# CAN.net
KiCad netlist of a schematic drawn in Altium Designer
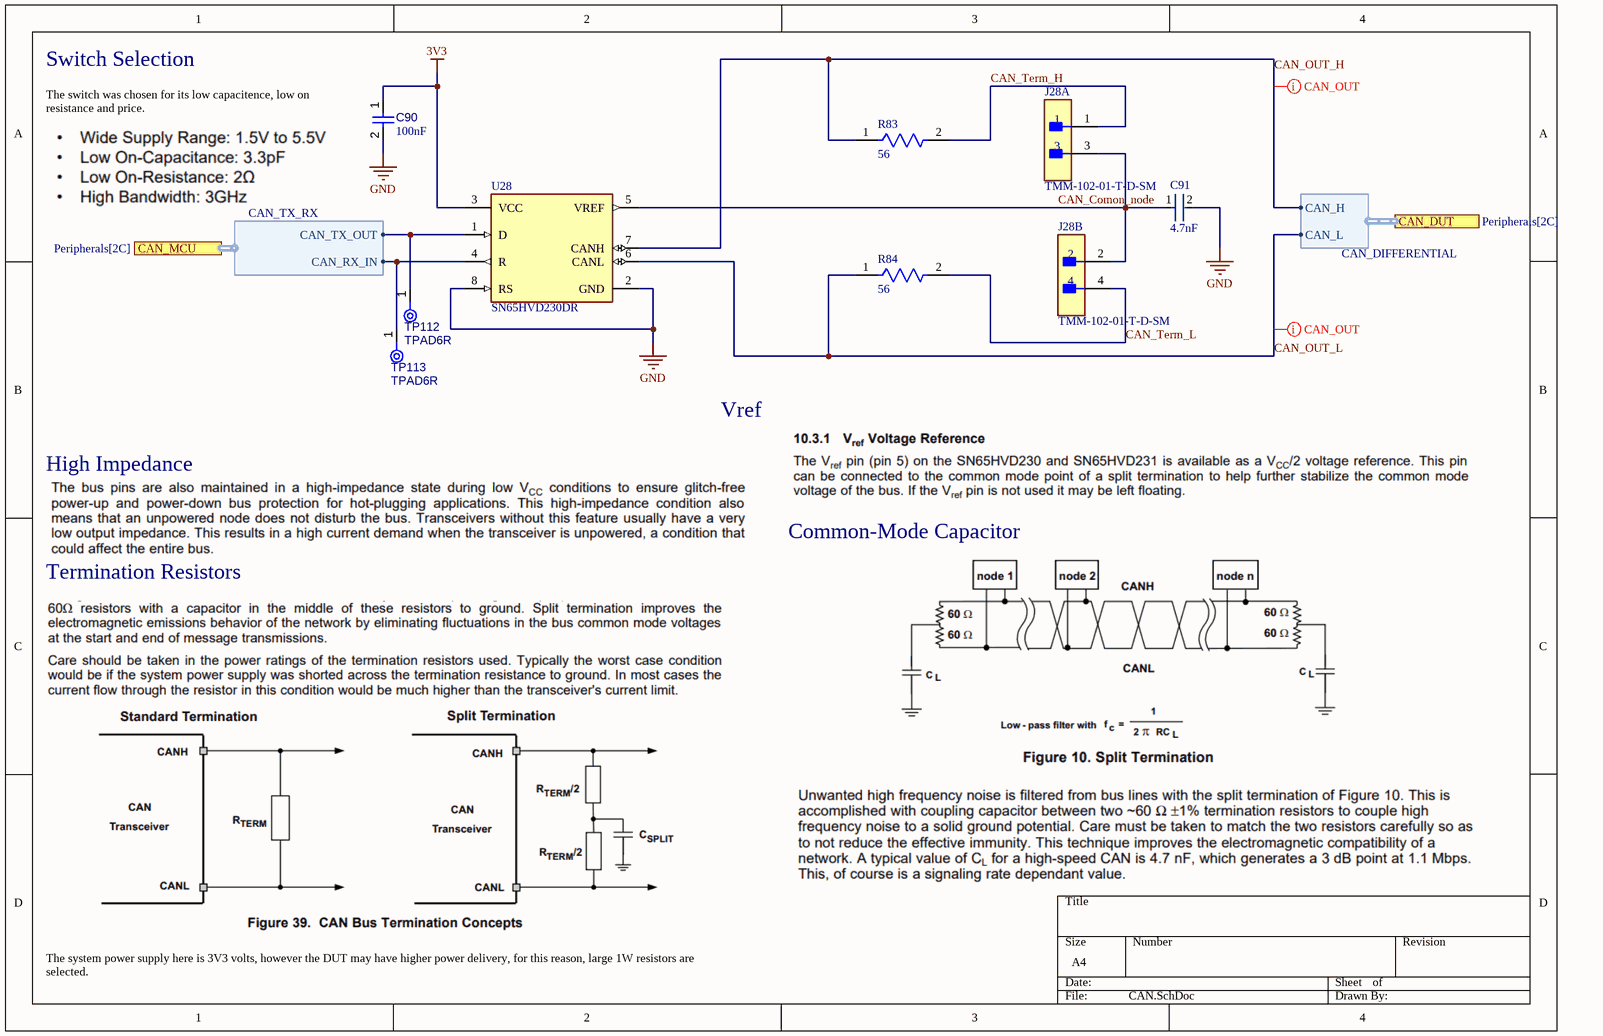
[diagram p0:  CAN.SchDoc]

(export (version "E")
  (design (tool "Eeschema 10.0.6"))
  (components
    (comp (ref "C90")
      (value "100nF")
      (footprint "CAPC1608X90X40NL10T20")
      (description "Chip Capacitor, 100 nF, +/- 10%, 50 V, 0603 (1608 Metric)")
      (fields (field (name "TOLERANCE") "10%") (field (name "Comment") "Capacitor 100 nF +/-10% 50 V 0603"))
      (libsource (lib "HIL RIG FYP") (part "CAP-NP-2"))
    )
    (comp (ref "C91")
      (value "4.7nF")
      (footprint "FP-C0603C-CF-MFG")
      (description "Ceramic Capacitor, Multilayer, Ceramic, 25V, 10% +Tol, 10% -Tol, C0G, 30Ppm/Cel Tc, 0.0047Uf,")
      (fields (field (name "TOLERANCE") "10%") (field (name "Comment") "C0603C472K3GACTU"))
      (libsource (lib "HIL RIG FYP") (part "b4654b650e69147ec39a6b967a45e02"))
    )
    (comp (ref "J28")
      (value "TMM-102-01-T-D-SM")
      (footprint "FP-TMM-102-01-T-D-SM-MFG")
      (description "CONN HEADER SMD 4POS 2MM")
      (libsource (lib "Altium Content Vault") (part "1621473add15499e993d6bbd36d0f06"))
    )
    (comp (ref "R83")
      (value "56")
      (footprint "FP-AC2512-IPC_C")
      (description "1W Thick Film Resistors 200V ±100ppm/℃ ±1% 56Ω 2512 Chip Resistor - Surface Mount ROHS")
      (fields (field (name "TOLERANCE") "1%") (field (name "Comment") "AC2512FK-0756RL"))
      (libsource (lib "HIL RIG FYP") (part "1029c3af85768c4190bb7ad29bc67b5"))
    )
    (comp (ref "R84")
      (value "56")
      (footprint "FP-AC2512-IPC_C")
      (description "1W Thick Film Resistors 200V ±100ppm/℃ ±1% 56Ω 2512 Chip Resistor - Surface Mount ROHS")
      (fields (field (name "TOLERANCE") "1%") (field (name "Comment") "AC2512FK-0756RL"))
      (libsource (lib "HIL RIG FYP") (part "1029c3af85768c4190bb7ad29bc67b5"))
    )
    (comp (ref "TP112")
      (value "TPAD6R")
      (footprint "TP06R")
      (description "0.6mm round")
      (libsource (lib "HIL RIG FYP") (part "CMP-001-0001-4"))
    )
    (comp (ref "TP113")
      (value "TPAD6R")
      (footprint "TP06R")
      (description "0.6mm round")
      (libsource (lib "HIL RIG FYP") (part "CMP-001-0001-4"))
    )
    (comp (ref "U28")
      (value "SN65HVD230DR")
      (footprint "FP-D0008A-IPC_A")
      (description "3.3 V CAN Transceiver with Standby Mode 8-SOIC -40 to 85")
      (libsource (lib "HIL RIG FYP") (part "43b56812b1adf0e60a7acfb7c27ab91"))
    )
  )
  (nets
    (net (code "3") (name "/CAN_Comon_node") (class "Default")
      (node (ref "C91") (pin "1") (pinfunction "1_1") (pintype "passive"))
      (node (ref "J28") (pin "2") (pinfunction "2_2") (pintype "passive"))
      (node (ref "J28") (pin "3") (pinfunction "3_3") (pintype "passive"))
      (node (ref "U28") (pin "5") (pinfunction "VREF_5") (pintype "output"))
    )
    (net (code "4") (name "/CAN_OUT_H") (class "Default")
      (node (ref "R83") (pin "1") (pinfunction "1_1") (pintype "passive"))
      (node (ref "U28") (pin "7") (pinfunction "CANH_7") (pintype "bidirectional"))
    )
    (net (code "5") (name "/CAN_OUT_L") (class "Default")
      (node (ref "R84") (pin "1") (pinfunction "1_1") (pintype "passive"))
      (node (ref "U28") (pin "6") (pinfunction "CANL_6") (pintype "bidirectional"))
    )
    (net (code "6") (name "/CAN_Term_H") (class "Default")
      (node (ref "J28") (pin "1") (pinfunction "1_1") (pintype "passive"))
      (node (ref "R83") (pin "2") (pinfunction "2_2") (pintype "passive"))
    )
    (net (code "7") (name "/CAN_Term_L") (class "Default")
      (node (ref "J28") (pin "4") (pinfunction "4_4") (pintype "passive"))
      (node (ref "R84") (pin "2") (pinfunction "2_2") (pintype "passive"))
    )
    (net (code "10") (name "3V3") (class "Default")
      (node (ref "C90") (pin "1") (pinfunction "1_1") (pintype "passive"))
      (node (ref "U28") (pin "3") (pinfunction "VCC_3") (pintype "power_in"))
    )
    (net (code "11") (name "GND") (class "Default")
      (node (ref "C90") (pin "2") (pinfunction "2_2") (pintype "passive"))
      (node (ref "C91") (pin "2") (pinfunction "2_2") (pintype "passive"))
      (node (ref "U28") (pin "2") (pinfunction "GND_2") (pintype "power_in"))
      (node (ref "U28") (pin "8") (pinfunction "RS_8") (pintype "input"))
    )
    (net (code "12") (name "Net-(TP112-TP)") (class "Default")
      (node (ref "TP112") (pin "1") (pinfunction "TP_1") (pintype "passive"))
      (node (ref "U28") (pin "1") (pinfunction "D_1") (pintype "input"))
    )
    (net (code "13") (name "Net-(TP113-TP)") (class "Default")
      (node (ref "TP113") (pin "1") (pinfunction "TP_1") (pintype "passive"))
      (node (ref "U28") (pin "4") (pinfunction "R_4") (pintype "output"))
    )
  )
)
